# AP-Taster_V3_3.net
KiCad netlist of a schematic drawn in EAGLE
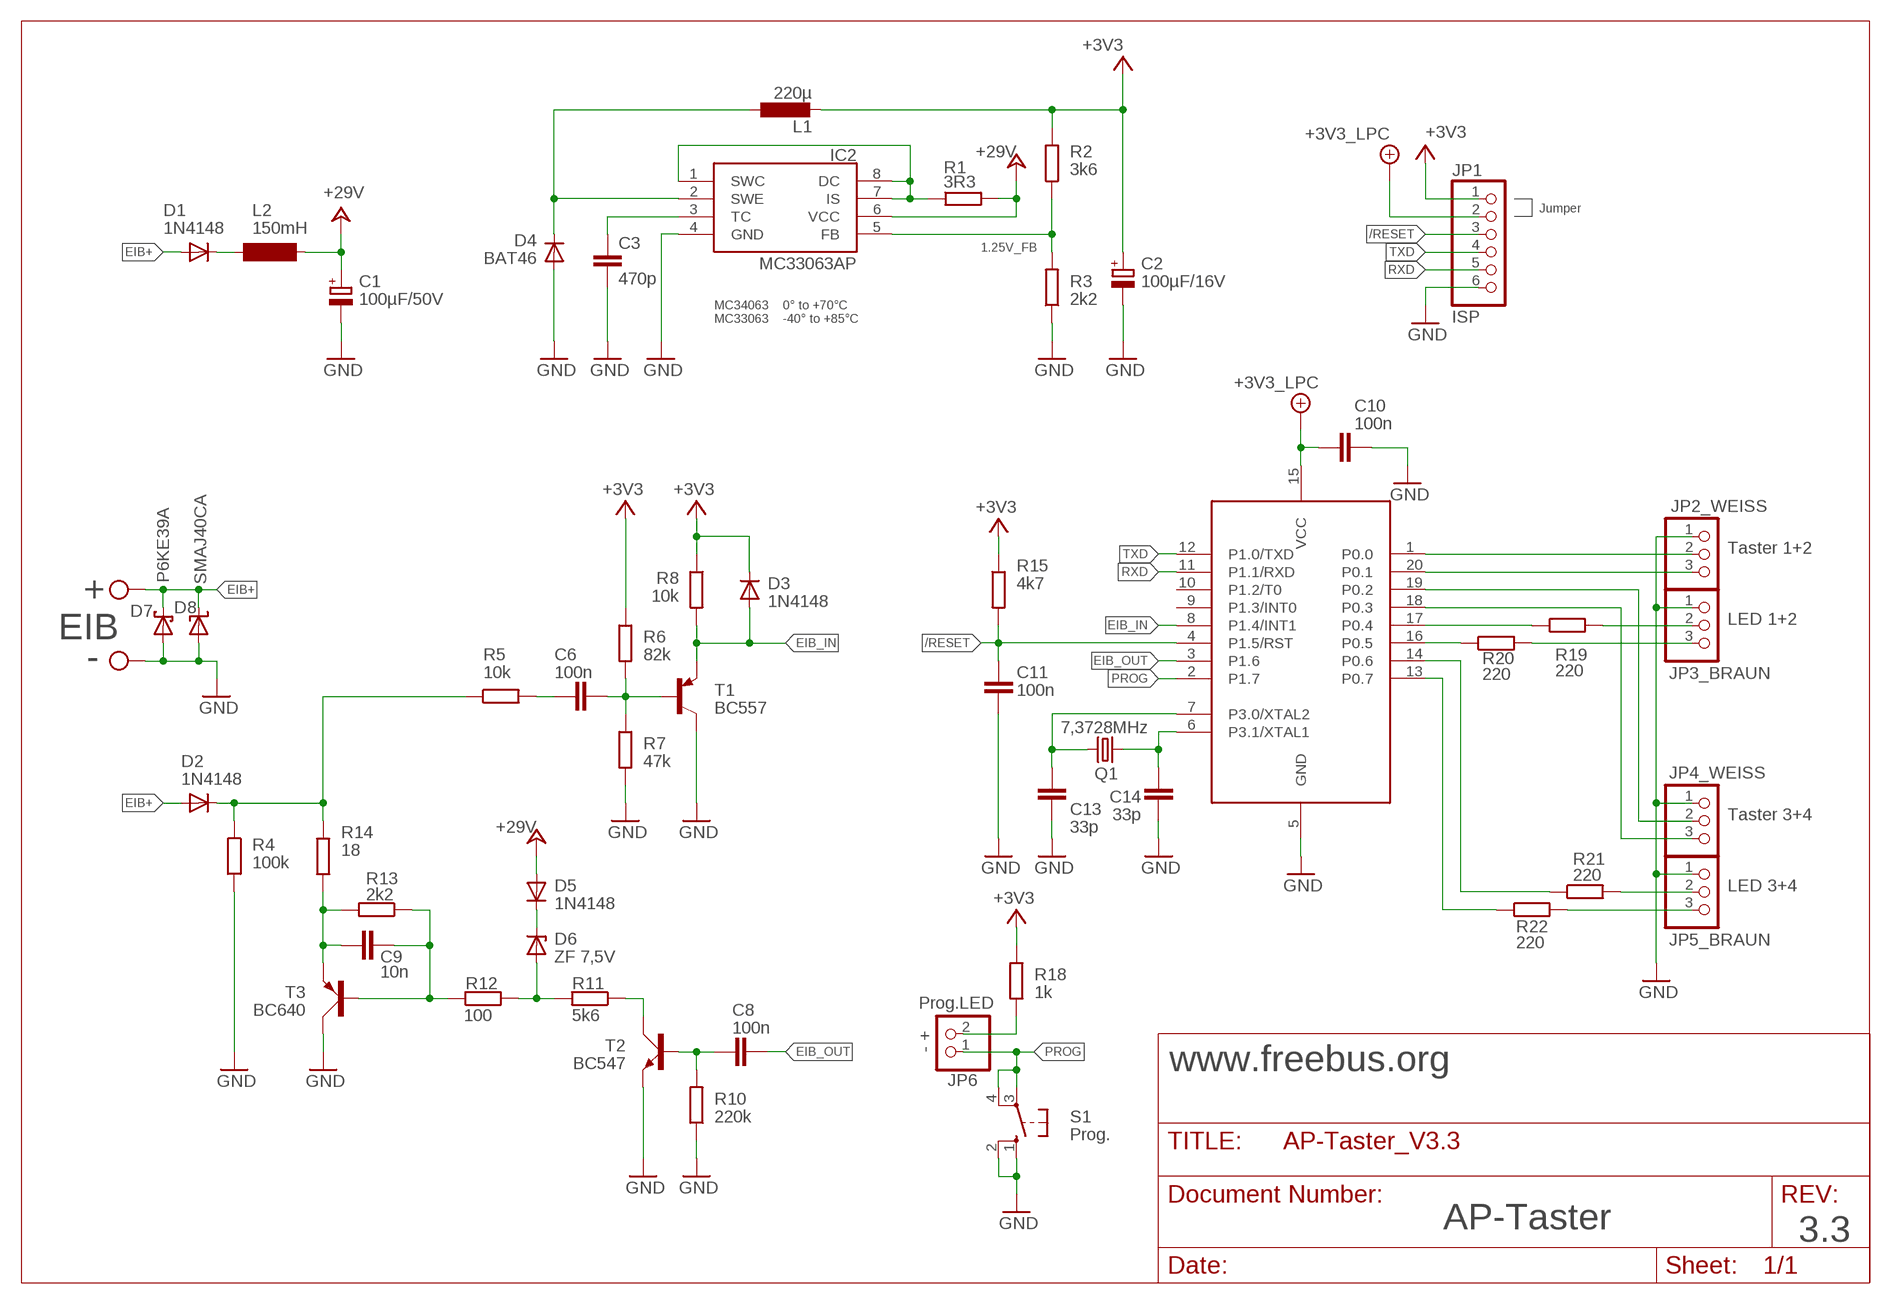
[diagram p0: schematic, sheet 1]

(export (version "E")
  (design (tool "Eeschema 10.0.6"))
  (components
    (comp (ref "C1")
      (value "100µF/50V")
      (footprint "eagle-import:E3,5-8")
      (libsource (lib "eagle-import") (part "CPOL-EUE3.5-8"))
    )
    (comp (ref "C2")
      (value "100µF/16V")
      (footprint "eagle-import:E2-5")
      (libsource (lib "eagle-import") (part "CPOL-EUE2-5"))
    )
    (comp (ref "C3")
      (value "470p")
      (footprint "eagle-import:C025-024X044")
      (libsource (lib "eagle-import") (part "C-EU025-024X044"))
    )
    (comp (ref "C6")
      (value "100n")
      (footprint "eagle-import:C050-024X044")
      (libsource (lib "eagle-import") (part "C-EU050-024X044"))
    )
    (comp (ref "C8")
      (value "100n")
      (footprint "eagle-import:C050-024X044")
      (libsource (lib "eagle-import") (part "C-EU050-024X044"))
    )
    (comp (ref "C9")
      (value "10n")
      (footprint "eagle-import:C025-024X044")
      (libsource (lib "eagle-import") (part "C-EU025-024X044"))
    )
    (comp (ref "C10")
      (value "100n")
      (footprint "eagle-import:C025-024X044")
      (libsource (lib "eagle-import") (part "C-EU025-024X044"))
    )
    (comp (ref "C11")
      (value "100n")
      (footprint "eagle-import:C025-024X044")
      (libsource (lib "eagle-import") (part "C-EU025-024X044"))
    )
    (comp (ref "C13")
      (value "33p")
      (footprint "eagle-import:C025-024X044")
      (libsource (lib "eagle-import") (part "C-EU025-024X044"))
    )
    (comp (ref "C14")
      (value "33p")
      (footprint "eagle-import:C025-024X044")
      (libsource (lib "eagle-import") (part "C-EU025-024X044"))
    )
    (comp (ref "D1")
      (value "1N4148")
      (footprint "eagle-import:DO34-7R")
      (libsource (lib "eagle-import") (part "DIODE-DO34-7R"))
    )
    (comp (ref "D2")
      (value "1N4148")
      (footprint "eagle-import:DO34-7R")
      (libsource (lib "eagle-import") (part "DIODE-DO34-7R"))
    )
    (comp (ref "D3")
      (value "1N4148")
      (footprint "eagle-import:DO34-7R")
      (libsource (lib "eagle-import") (part "DIODE-DO34-7R"))
    )
    (comp (ref "D4")
      (value "BAT46")
      (footprint "eagle-import:DO34-7R")
      (libsource (lib "eagle-import") (part "DIODE-DO34-7R"))
    )
    (comp (ref "D5")
      (value "1N4148")
      (footprint "eagle-import:DO34-7R")
      (libsource (lib "eagle-import") (part "DIODE-DO34-7R"))
    )
    (comp (ref "D6")
      (value "ZF 7,5V")
      (footprint "eagle-import:DO34Z7R")
      (libsource (lib "eagle-import") (part "ZENER-DIODEDO34Z7R"))
    )
    (comp (ref "D7")
      (value "P6KE39A")
      (footprint "eagle-import:DO35-7G")
      (libsource (lib "eagle-import") (part "P6KEXX7MM"))
    )
    (comp (ref "D8")
      (value "SMAJ40CA")
      (footprint "eagle-import:SMBJ")
      (libsource (lib "eagle-import") (part "SUPPRESSOR-SMBJ"))
    )
    (comp (ref "IC1")
      (value "89LPC922")
      (footprint "eagle-import:DIL20")
      (libsource (lib "eagle-import") (part "89LPC922"))
    )
    (comp (ref "IC2")
      (value "MC33063AP")
      (footprint "eagle-import:DIL08")
      (libsource (lib "eagle-import") (part "MC34063AP"))
    )
    (comp (ref "JP1")
      (value "ISP")
      (footprint "eagle-import:1X06")
      (libsource (lib "eagle-import") (part "PINHD-1X6"))
    )
    (comp (ref "JP2_WEISS")
      (value "Taster 1+2")
      (footprint "eagle-import:1X03_CONNECTOR")
      (libsource (lib "eagle-import") (part "PINHD-1X3CON"))
    )
    (comp (ref "JP3_BRAUN")
      (value "LED 1+2")
      (footprint "eagle-import:1X03_CONNECTOR")
      (libsource (lib "eagle-import") (part "PINHD-1X3CON"))
    )
    (comp (ref "JP4_WEISS")
      (value "Taster 3+4")
      (footprint "eagle-import:1X03_CONNECTOR")
      (libsource (lib "eagle-import") (part "PINHD-1X3CON"))
    )
    (comp (ref "JP5_BRAUN")
      (value "LED 3+4")
      (footprint "eagle-import:1X03_CONNECTOR")
      (libsource (lib "eagle-import") (part "PINHD-1X3CON"))
    )
    (comp (ref "JP6")
      (value "Prog.LED")
      (footprint "eagle-import:1X02_CONNECTOR")
      (libsource (lib "eagle-import") (part "PINHD-1X2CON"))
    )
    (comp (ref "L1")
      (value "220µ")
      (footprint "eagle-import:0207_10")
      (libsource (lib "eagle-import") (part "L-EU0207/10"))
    )
    (comp (ref "L2")
      (value "150mH")
      (footprint "eagle-import:BS11")
      (libsource (lib "eagle-import") (part "BS11"))
    )
    (comp (ref "Q1")
      (value "7,3728MHz")
      (footprint "eagle-import:HC49_S")
      (libsource (lib "eagle-import") (part "CRYSTALHC49S"))
    )
    (comp (ref "R1")
      (value "3R3")
      (footprint "eagle-import:0207_7")
      (libsource (lib "eagle-import") (part "R-EU_0207/7"))
    )
    (comp (ref "R2")
      (value "3k6")
      (footprint "eagle-import:0207_7")
      (libsource (lib "eagle-import") (part "R-EU_0207/7"))
    )
    (comp (ref "R3")
      (value "2k2")
      (footprint "eagle-import:0207_7")
      (libsource (lib "eagle-import") (part "R-EU_0207/7"))
    )
    (comp (ref "R4")
      (value "100k")
      (footprint "eagle-import:0207_7")
      (libsource (lib "eagle-import") (part "R-EU_0207/7"))
    )
    (comp (ref "R5")
      (value "10k")
      (footprint "eagle-import:0207_7")
      (libsource (lib "eagle-import") (part "R-EU_0207/7"))
    )
    (comp (ref "R6")
      (value "82k")
      (footprint "eagle-import:0207_7")
      (libsource (lib "eagle-import") (part "R-EU_0207/7"))
    )
    (comp (ref "R7")
      (value "47k")
      (footprint "eagle-import:0207_7")
      (libsource (lib "eagle-import") (part "R-EU_0207/7"))
    )
    (comp (ref "R8")
      (value "10k")
      (footprint "eagle-import:0207_7")
      (libsource (lib "eagle-import") (part "R-EU_0207/7"))
    )
    (comp (ref "R10")
      (value "220k")
      (footprint "eagle-import:0207_7")
      (libsource (lib "eagle-import") (part "R-EU_0207/7"))
    )
    (comp (ref "R11")
      (value "5k6")
      (footprint "eagle-import:0207_7")
      (libsource (lib "eagle-import") (part "R-EU_0207/7"))
    )
    (comp (ref "R12")
      (value "100")
      (footprint "eagle-import:0207_7")
      (libsource (lib "eagle-import") (part "R-EU_0207/7"))
    )
    (comp (ref "R13")
      (value "2k2")
      (footprint "eagle-import:0207_7")
      (libsource (lib "eagle-import") (part "R-EU_0207/7"))
    )
    (comp (ref "R14")
      (value "18")
      (footprint "eagle-import:0207_7")
      (libsource (lib "eagle-import") (part "R-EU_0207/7"))
    )
    (comp (ref "R15")
      (value "4k7")
      (footprint "eagle-import:0207_7")
      (libsource (lib "eagle-import") (part "R-EU_0207/7"))
    )
    (comp (ref "R18")
      (value "1k")
      (footprint "eagle-import:0207_7")
      (libsource (lib "eagle-import") (part "R-EU_0207/7"))
    )
    (comp (ref "R19")
      (value "220")
      (footprint "eagle-import:0207_7")
      (libsource (lib "eagle-import") (part "R-EU_0207/7"))
    )
    (comp (ref "R20")
      (value "220")
      (footprint "eagle-import:0207_7")
      (libsource (lib "eagle-import") (part "R-EU_0207/7"))
    )
    (comp (ref "R21")
      (value "220")
      (footprint "eagle-import:0207_7")
      (libsource (lib "eagle-import") (part "R-EU_0207/7"))
    )
    (comp (ref "R22")
      (value "220")
      (footprint "eagle-import:0207_7")
      (libsource (lib "eagle-import") (part "R-EU_0207/7"))
    )
    (comp (ref "S1")
      (value "Prog.")
      (footprint "eagle-import:B3F-10XX")
      (fields (field (name "MPN") "B3F-1000"))
      (libsource (lib "eagle-import") (part "10-XX"))
    )
    (comp (ref "T1")
      (value "BC557")
      (footprint "eagle-import:TO92")
      (libsource (lib "eagle-import") (part "BC557"))
    )
    (comp (ref "T2")
      (value "BC547")
      (footprint "eagle-import:SOT54A")
      (libsource (lib "eagle-import") (part "BC547"))
    )
    (comp (ref "T3")
      (value "BC640")
      (footprint "eagle-import:SOT54D")
      (libsource (lib "eagle-import") (part "BC640"))
    )
    (comp (ref "X1")
      (value "EIB")
      (footprint "eagle-import:W237-102")
      (fields (field (name "MPN") "237-102"))
      (libsource (lib "eagle-import") (part "W237-102"))
    )
  )
  (nets
    (net (code "1") (name "+3V3") (class "Default")
      (node (ref "C2") (pin "+") (pinfunction "+_+") (pintype "passive"))
      (node (ref "D3") (pin "C") (pinfunction "C_C") (pintype "passive"))
      (node (ref "JP1") (pin "1") (pinfunction "1_1") (pintype "passive"))
      (node (ref "L1") (pin "2") (pinfunction "2_2") (pintype "passive"))
      (node (ref "R15") (pin "1") (pinfunction "1_1") (pintype "passive"))
      (node (ref "R18") (pin "1") (pinfunction "1_1") (pintype "passive"))
      (node (ref "R2") (pin "2") (pinfunction "2_2") (pintype "passive"))
      (node (ref "R6") (pin "1") (pinfunction "1_1") (pintype "passive"))
      (node (ref "R8") (pin "1") (pinfunction "1_1") (pintype "passive"))
    )
    (net (code "2") (name "+3V3_LPC") (class "Default")
      (node (ref "C10") (pin "2") (pinfunction "2_2") (pintype "passive"))
      (node (ref "IC1") (pin "15") (pinfunction "VCC_15") (pintype "bidirectional"))
      (node (ref "JP1") (pin "2") (pinfunction "2_2") (pintype "passive"))
    )
    (net (code "3") (name "+29V") (class "Default")
      (node (ref "C1") (pin "+") (pinfunction "+_+") (pintype "passive"))
      (node (ref "D5") (pin "A") (pinfunction "A_A") (pintype "passive"))
      (node (ref "IC2") (pin "6") (pinfunction "VCC_6") (pintype "passive"))
      (node (ref "L2") (pin "2") (pinfunction "2_2") (pintype "passive"))
      (node (ref "R1") (pin "2") (pinfunction "2_2") (pintype "passive"))
    )
    (net (code "4") (name "/1.25V_FB") (class "Default")
      (node (ref "IC2") (pin "5") (pinfunction "FB_5") (pintype "passive"))
      (node (ref "R2") (pin "1") (pinfunction "1_1") (pintype "passive"))
      (node (ref "R3") (pin "2") (pinfunction "2_2") (pintype "passive"))
    )
    (net (code "5") (name "EIB+") (class "Default")
      (node (ref "D1") (pin "A") (pinfunction "A_A") (pintype "passive"))
      (node (ref "D2") (pin "A") (pinfunction "A_A") (pintype "passive"))
      (node (ref "D7") (pin "C") (pinfunction "C_C") (pintype "passive"))
      (node (ref "D8") (pin "C") (pinfunction "C_C") (pintype "passive"))
      (node (ref "X1") (pin "2") (pinfunction "KL_2") (pintype "passive"))
    )
    (net (code "6") (name "EIB_IN") (class "Default")
      (node (ref "D3") (pin "A") (pinfunction "A_A") (pintype "passive"))
      (node (ref "IC1") (pin "8") (pinfunction "P1.4/INT1_8") (pintype "bidirectional"))
      (node (ref "R8") (pin "2") (pinfunction "2_2") (pintype "passive"))
      (node (ref "T1") (pin "1") (pinfunction "E_1") (pintype "passive"))
    )
    (net (code "7") (name "EIB_OUT") (class "Default")
      (node (ref "C8") (pin "2") (pinfunction "2_2") (pintype "passive"))
      (node (ref "IC1") (pin "3") (pinfunction "P1.6_3") (pintype "bidirectional"))
    )
    (net (code "8") (name "GND") (class "Default")
      (node (ref "C1") (pin "-") (pinfunction "-_-") (pintype "passive"))
      (node (ref "C10") (pin "1") (pinfunction "1_1") (pintype "passive"))
      (node (ref "C11") (pin "1") (pinfunction "1_1") (pintype "passive"))
      (node (ref "C13") (pin "2") (pinfunction "2_2") (pintype "passive"))
      (node (ref "C14") (pin "2") (pinfunction "2_2") (pintype "passive"))
      (node (ref "C2") (pin "-") (pinfunction "-_-") (pintype "passive"))
      (node (ref "C3") (pin "2") (pinfunction "2_2") (pintype "passive"))
      (node (ref "D4") (pin "A") (pinfunction "A_A") (pintype "passive"))
      (node (ref "D7") (pin "A") (pinfunction "A_A") (pintype "passive"))
      (node (ref "D8") (pin "A") (pinfunction "A_A") (pintype "passive"))
      (node (ref "IC1") (pin "5") (pinfunction "GND_5") (pintype "bidirectional"))
      (node (ref "IC2") (pin "4") (pinfunction "GND_4") (pintype "passive"))
      (node (ref "JP1") (pin "6") (pinfunction "6_6") (pintype "passive"))
      (node (ref "JP2_WEISS") (pin "1") (pinfunction "1_1") (pintype "passive"))
      (node (ref "JP3_BRAUN") (pin "1") (pinfunction "1_1") (pintype "passive"))
      (node (ref "JP4_WEISS") (pin "1") (pinfunction "1_1") (pintype "passive"))
      (node (ref "JP5_BRAUN") (pin "1") (pinfunction "1_1") (pintype "passive"))
      (node (ref "R10") (pin "1") (pinfunction "1_1") (pintype "passive"))
      (node (ref "R3") (pin "1") (pinfunction "1_1") (pintype "passive"))
      (node (ref "R4") (pin "2") (pinfunction "2_2") (pintype "passive"))
      (node (ref "R7") (pin "2") (pinfunction "2_2") (pintype "passive"))
      (node (ref "S1") (pin "1") (pinfunction "S_1") (pintype "passive"))
      (node (ref "S1") (pin "2") (pinfunction "S1_2") (pintype "passive"))
      (node (ref "T1") (pin "3") (pinfunction "C_3") (pintype "passive"))
      (node (ref "T2") (pin "E") (pinfunction "E_E") (pintype "passive"))
      (node (ref "T3") (pin "C") (pinfunction "C_C") (pintype "passive"))
      (node (ref "X1") (pin "1") (pinfunction "KL_1") (pintype "passive"))
    )
    (net (code "9") (name "Net-(C6-Pad1)") (class "Default")
      (node (ref "C6") (pin "1") (pinfunction "1_1") (pintype "passive"))
      (node (ref "R5") (pin "2") (pinfunction "2_2") (pintype "passive"))
    )
    (net (code "10") (name "Net-(C8-Pad1)") (class "Default")
      (node (ref "C8") (pin "1") (pinfunction "1_1") (pintype "passive"))
      (node (ref "R10") (pin "2") (pinfunction "2_2") (pintype "passive"))
      (node (ref "T2") (pin "B") (pinfunction "B_B") (pintype "passive"))
    )
    (net (code "11") (name "Net-(C9-Pad1)") (class "Default")
      (node (ref "C9") (pin "1") (pinfunction "1_1") (pintype "passive"))
      (node (ref "R12") (pin "1") (pinfunction "1_1") (pintype "passive"))
      (node (ref "R13") (pin "1") (pinfunction "1_1") (pintype "passive"))
      (node (ref "T3") (pin "B") (pinfunction "B_B") (pintype "passive"))
    )
    (net (code "12") (name "Net-(C9-Pad2)") (class "Default")
      (node (ref "C9") (pin "2") (pinfunction "2_2") (pintype "passive"))
      (node (ref "R13") (pin "2") (pinfunction "2_2") (pintype "passive"))
      (node (ref "R14") (pin "2") (pinfunction "2_2") (pintype "passive"))
      (node (ref "T3") (pin "E") (pinfunction "E_E") (pintype "passive"))
    )
    (net (code "13") (name "Net-(D1-PadC)") (class "Default")
      (node (ref "D1") (pin "C") (pinfunction "C_C") (pintype "passive"))
      (node (ref "L2") (pin "1") (pinfunction "1_1") (pintype "passive"))
    )
    (net (code "14") (name "Net-(D2-PadC)") (class "Default")
      (node (ref "D2") (pin "C") (pinfunction "C_C") (pintype "passive"))
      (node (ref "R14") (pin "1") (pinfunction "1_1") (pintype "passive"))
      (node (ref "R4") (pin "1") (pinfunction "1_1") (pintype "passive"))
      (node (ref "R5") (pin "1") (pinfunction "1_1") (pintype "passive"))
    )
    (net (code "15") (name "Net-(D5-PadC)") (class "Default")
      (node (ref "D5") (pin "C") (pinfunction "C_C") (pintype "passive"))
      (node (ref "D6") (pin "C") (pinfunction "C_C") (pintype "passive"))
    )
    (net (code "16") (name "Net-(D6-PadA)") (class "Default")
      (node (ref "D6") (pin "A") (pinfunction "A_A") (pintype "passive"))
      (node (ref "R11") (pin "2") (pinfunction "2_2") (pintype "passive"))
      (node (ref "R12") (pin "2") (pinfunction "2_2") (pintype "passive"))
    )
    (net (code "17") (name "Net-(IC1-P0.0)") (class "Default")
      (node (ref "IC1") (pin "1") (pinfunction "P0.0_1") (pintype "bidirectional"))
      (node (ref "JP2_WEISS") (pin "2") (pinfunction "2_2") (pintype "passive"))
    )
    (net (code "18") (name "Net-(IC1-P0.1)") (class "Default")
      (node (ref "IC1") (pin "20") (pinfunction "P0.1_20") (pintype "bidirectional"))
      (node (ref "JP2_WEISS") (pin "3") (pinfunction "3_3") (pintype "passive"))
    )
    (net (code "19") (name "Net-(IC1-P0.2)") (class "Default")
      (node (ref "IC1") (pin "19") (pinfunction "P0.2_19") (pintype "bidirectional"))
      (node (ref "JP4_WEISS") (pin "2") (pinfunction "2_2") (pintype "passive"))
    )
    (net (code "20") (name "Net-(IC1-P0.3)") (class "Default")
      (node (ref "IC1") (pin "18") (pinfunction "P0.3_18") (pintype "bidirectional"))
      (node (ref "JP4_WEISS") (pin "3") (pinfunction "3_3") (pintype "passive"))
    )
    (net (code "21") (name "Net-(IC1-P0.4)") (class "Default")
      (node (ref "IC1") (pin "17") (pinfunction "P0.4_17") (pintype "bidirectional"))
      (node (ref "R19") (pin "1") (pinfunction "1_1") (pintype "passive"))
    )
    (net (code "22") (name "Net-(IC1-P0.5)") (class "Default")
      (node (ref "IC1") (pin "16") (pinfunction "P0.5_16") (pintype "bidirectional"))
      (node (ref "R20") (pin "1") (pinfunction "1_1") (pintype "passive"))
    )
    (net (code "23") (name "Net-(IC1-P0.6)") (class "Default")
      (node (ref "IC1") (pin "14") (pinfunction "P0.6_14") (pintype "bidirectional"))
      (node (ref "R21") (pin "1") (pinfunction "1_1") (pintype "passive"))
    )
    (net (code "24") (name "Net-(IC1-P0.7)") (class "Default")
      (node (ref "IC1") (pin "13") (pinfunction "P0.7_13") (pintype "bidirectional"))
      (node (ref "R22") (pin "1") (pinfunction "1_1") (pintype "passive"))
    )
    (net (code "25") (name "Net-(IC1-P3.0{slash}XTAL2)") (class "Default")
      (node (ref "C13") (pin "1") (pinfunction "1_1") (pintype "passive"))
      (node (ref "IC1") (pin "7") (pinfunction "P3.0/XTAL2_7") (pintype "bidirectional"))
      (node (ref "Q1") (pin "2") (pinfunction "2_2") (pintype "passive"))
    )
    (net (code "26") (name "Net-(IC1-P3.1{slash}XTAL1)") (class "Default")
      (node (ref "C14") (pin "1") (pinfunction "1_1") (pintype "passive"))
      (node (ref "IC1") (pin "6") (pinfunction "P3.1/XTAL1_6") (pintype "bidirectional"))
      (node (ref "Q1") (pin "1") (pinfunction "1_1") (pintype "passive"))
    )
    (net (code "27") (name "Net-(IC2-DC)") (class "Default")
      (node (ref "IC2") (pin "1") (pinfunction "SWC_1") (pintype "passive"))
      (node (ref "IC2") (pin "7") (pinfunction "IS_7") (pintype "passive"))
      (node (ref "IC2") (pin "8") (pinfunction "DC_8") (pintype "passive"))
      (node (ref "R1") (pin "1") (pinfunction "1_1") (pintype "passive"))
    )
    (net (code "28") (name "Net-(IC2-SWE)") (class "Default")
      (node (ref "D4") (pin "C") (pinfunction "C_C") (pintype "passive"))
      (node (ref "IC2") (pin "2") (pinfunction "SWE_2") (pintype "passive"))
      (node (ref "L1") (pin "1") (pinfunction "1_1") (pintype "passive"))
    )
    (net (code "29") (name "Net-(IC2-TC)") (class "Default")
      (node (ref "C3") (pin "1") (pinfunction "1_1") (pintype "passive"))
      (node (ref "IC2") (pin "3") (pinfunction "TC_3") (pintype "passive"))
    )
    (net (code "30") (name "Net-(JP3_BRAUN-Pad2)") (class "Default")
      (node (ref "JP3_BRAUN") (pin "2") (pinfunction "2_2") (pintype "passive"))
      (node (ref "R19") (pin "2") (pinfunction "2_2") (pintype "passive"))
    )
    (net (code "31") (name "Net-(JP3_BRAUN-Pad3)") (class "Default")
      (node (ref "JP3_BRAUN") (pin "3") (pinfunction "3_3") (pintype "passive"))
      (node (ref "R20") (pin "2") (pinfunction "2_2") (pintype "passive"))
    )
    (net (code "32") (name "Net-(JP5_BRAUN-Pad2)") (class "Default")
      (node (ref "JP5_BRAUN") (pin "2") (pinfunction "2_2") (pintype "passive"))
      (node (ref "R21") (pin "2") (pinfunction "2_2") (pintype "passive"))
    )
    (net (code "33") (name "Net-(JP5_BRAUN-Pad3)") (class "Default")
      (node (ref "JP5_BRAUN") (pin "3") (pinfunction "3_3") (pintype "passive"))
      (node (ref "R22") (pin "2") (pinfunction "2_2") (pintype "passive"))
    )
    (net (code "34") (name "Net-(JP6-Pad2)") (class "Default")
      (node (ref "JP6") (pin "2") (pinfunction "2_2") (pintype "passive"))
      (node (ref "R18") (pin "2") (pinfunction "2_2") (pintype "passive"))
    )
    (net (code "35") (name "Net-(R11-Pad1)") (class "Default")
      (node (ref "R11") (pin "1") (pinfunction "1_1") (pintype "passive"))
      (node (ref "T2") (pin "C") (pinfunction "C_C") (pintype "passive"))
    )
    (net (code "36") (name "Net-(T1-B)") (class "Default")
      (node (ref "C6") (pin "2") (pinfunction "2_2") (pintype "passive"))
      (node (ref "R6") (pin "2") (pinfunction "2_2") (pintype "passive"))
      (node (ref "R7") (pin "1") (pinfunction "1_1") (pintype "passive"))
      (node (ref "T1") (pin "2") (pinfunction "B_2") (pintype "passive"))
    )
    (net (code "37") (name "PROG") (class "Default")
      (node (ref "IC1") (pin "2") (pinfunction "P1.7_2") (pintype "bidirectional"))
      (node (ref "JP6") (pin "1") (pinfunction "1_1") (pintype "passive"))
      (node (ref "S1") (pin "3") (pinfunction "P_3") (pintype "passive"))
      (node (ref "S1") (pin "4") (pinfunction "P1_4") (pintype "passive"))
    )
    (net (code "38") (name "RXD") (class "Default")
      (node (ref "IC1") (pin "11") (pinfunction "P1.1/RXD_11") (pintype "bidirectional"))
      (node (ref "JP1") (pin "5") (pinfunction "5_5") (pintype "passive"))
    )
    (net (code "39") (name "TXD") (class "Default")
      (node (ref "IC1") (pin "12") (pinfunction "P1.0/TXD_12") (pintype "bidirectional"))
      (node (ref "JP1") (pin "4") (pinfunction "4_4") (pintype "passive"))
    )
    (net (code "40") (name "unconnected-(IC1-P1.2{slash}T0-Pad10)") (class "Default")
      (node (ref "IC1") (pin "10") (pinfunction "P1.2/T0_10") (pintype "bidirectional"))
    )
    (net (code "41") (name "unconnected-(IC1-P1.3{slash}INT0-Pad9)") (class "Default")
      (node (ref "IC1") (pin "9") (pinfunction "P1.3/INT0_9") (pintype "bidirectional"))
    )
    (net (code "42") (name "{slash}RESET") (class "Default")
      (node (ref "C11") (pin "2") (pinfunction "2_2") (pintype "passive"))
      (node (ref "IC1") (pin "4") (pinfunction "P1.5/RST_4") (pintype "bidirectional"))
      (node (ref "JP1") (pin "3") (pinfunction "3_3") (pintype "passive"))
      (node (ref "R15") (pin "2") (pinfunction "2_2") (pintype "passive"))
    )
  )
)
